# schematic.net
KiCad netlist of a schematic drawn in Altium Designer
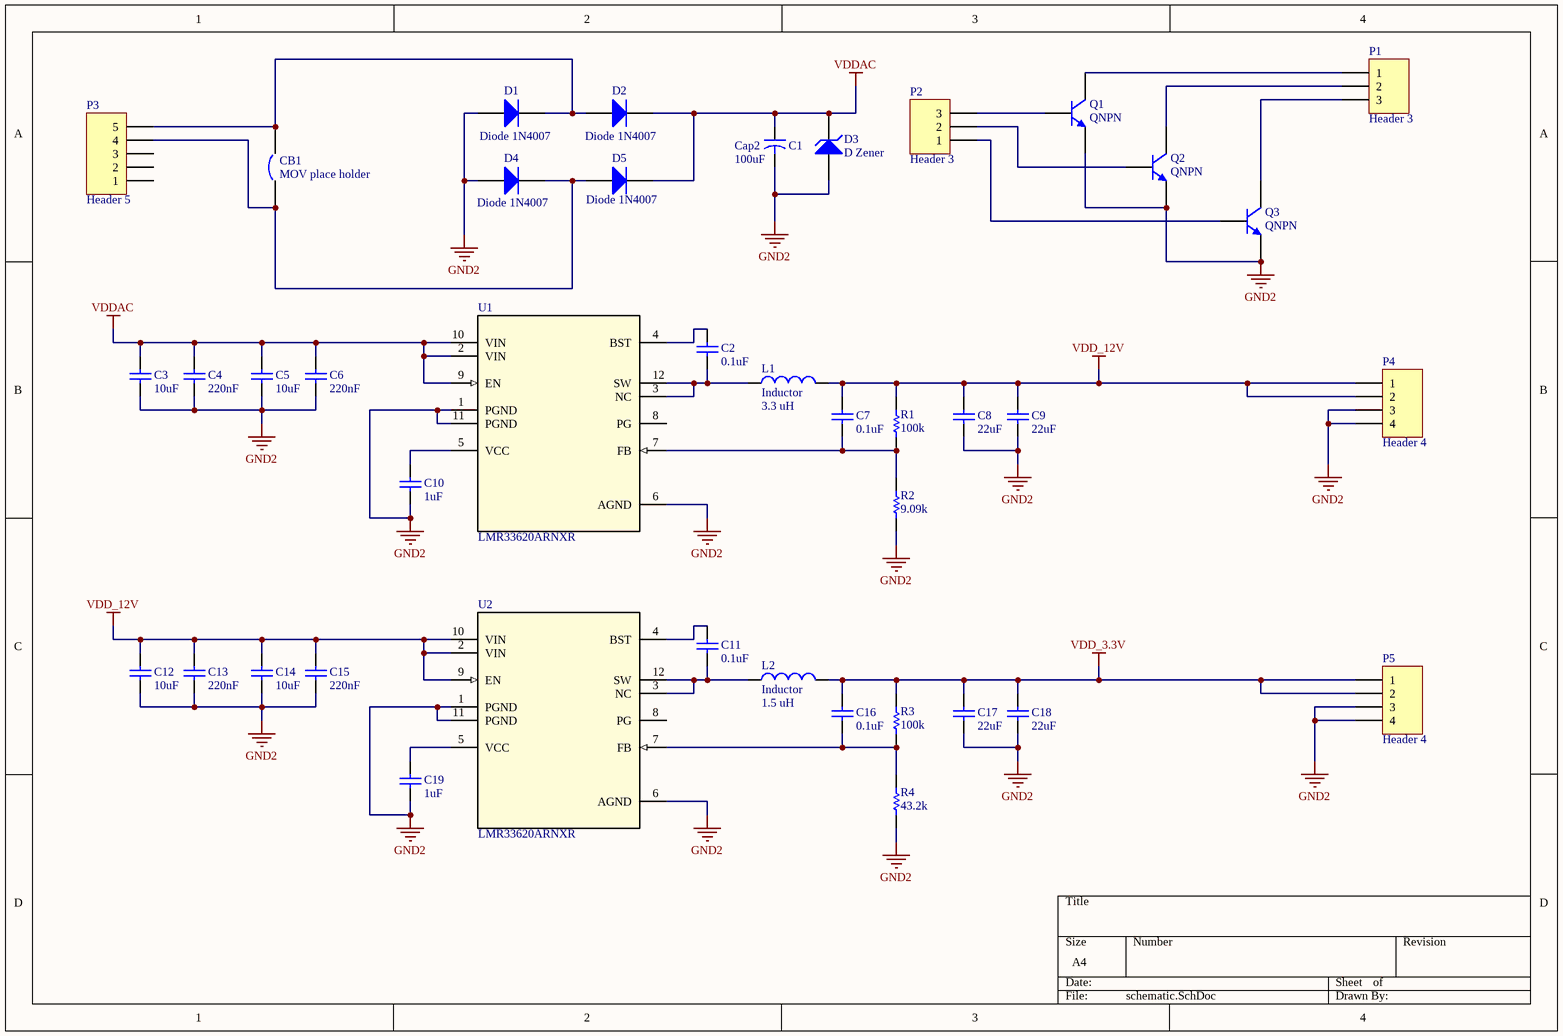
[diagram p0: schematic.SchDoc]

(export (version "E")
  (design (tool "Eeschema 10.0.6"))
  (components
    (comp (ref "C1")
      (value "Cap2")
      (footprint "CAPR5-4X5")
      (description "Capacitor")
      (fields (field (name "ALTIUM_VALUE") "100uF") (field (name "PUBLISHER") "Altium Limited"))
      (libsource (lib "Miscellaneous Devices") (part "Cap2"))
    )
    (comp (ref "C2")
      (value "0.1uF")
      (footprint "C_0402")
      (libsource (lib "Miscellaneous Devices") (part "Cap"))
    )
    (comp (ref "C3")
      (value "10uF")
      (footprint "CAPC1608X05N")
      (libsource (lib "Miscellaneous Devices") (part "Cap"))
    )
    (comp (ref "C4")
      (value "220nF")
      (footprint "C_0402")
      (libsource (lib "Miscellaneous Devices") (part "Cap"))
    )
    (comp (ref "C5")
      (value "10uF")
      (footprint "CAPC1608X05N")
      (libsource (lib "Miscellaneous Devices") (part "Cap"))
    )
    (comp (ref "C6")
      (value "220nF")
      (footprint "C_0402")
      (libsource (lib "Miscellaneous Devices") (part "Cap"))
    )
    (comp (ref "C7")
      (value "0.1uF")
      (footprint "C_0402")
      (libsource (lib "Miscellaneous Devices") (part "Cap"))
    )
    (comp (ref "C8")
      (value "22uF")
      (footprint "CAPC1608X05N")
      (libsource (lib "Miscellaneous Devices") (part "Cap"))
    )
    (comp (ref "C9")
      (value "22uF")
      (footprint "CAPC1608X05N")
      (libsource (lib "Miscellaneous Devices") (part "Cap"))
    )
    (comp (ref "C10")
      (value "1uF")
      (footprint "C_0402")
      (libsource (lib "Miscellaneous Devices") (part "Cap"))
    )
    (comp (ref "C11")
      (value "0.1uF")
      (footprint "C_0402")
      (libsource (lib "Miscellaneous Devices") (part "Cap"))
    )
    (comp (ref "C12")
      (value "10uF")
      (footprint "CAPC1608X05N")
      (libsource (lib "Miscellaneous Devices") (part "Cap"))
    )
    (comp (ref "C13")
      (value "220nF")
      (footprint "C_0402")
      (libsource (lib "Miscellaneous Devices") (part "Cap"))
    )
    (comp (ref "C14")
      (value "10uF")
      (footprint "CAPC1608X05N")
      (libsource (lib "Miscellaneous Devices") (part "Cap"))
    )
    (comp (ref "C15")
      (value "220nF")
      (footprint "C_0402")
      (libsource (lib "Miscellaneous Devices") (part "Cap"))
    )
    (comp (ref "C16")
      (value "0.1uF")
      (footprint "C_0402")
      (libsource (lib "Miscellaneous Devices") (part "Cap"))
    )
    (comp (ref "C17")
      (value "22uF")
      (footprint "CAPC1608X05N")
      (libsource (lib "Miscellaneous Devices") (part "Cap"))
    )
    (comp (ref "C18")
      (value "22uF")
      (footprint "CAPC1608X05N")
      (libsource (lib "Miscellaneous Devices") (part "Cap"))
    )
    (comp (ref "C19")
      (value "1uF")
      (footprint "C_0402")
      (libsource (lib "Miscellaneous Devices") (part "Cap"))
    )
    (comp (ref "CB1")
      (value "MOV place holder")
      (footprint "mov")
      (description "Circuit Breaker")
      (fields (field (name "PUBLISHER") "Altium Limited"))
      (libsource (lib "Miscellaneous Devices") (part "Circuit Breaker"))
    )
    (comp (ref "D1")
      (value "Diode 1N4007")
      (footprint "DO-41")
      (description "1 Amp General Purpose Rectifier")
      (fields (field (name "PUBLISHER") "Altium Limited"))
      (libsource (lib "Miscellaneous Devices") (part "Diode 1N4007"))
    )
    (comp (ref "D2")
      (value "Diode 1N4007")
      (footprint "DO-41")
      (description "1 Amp General Purpose Rectifier")
      (fields (field (name "PUBLISHER") "Altium Limited"))
      (libsource (lib "Miscellaneous Devices") (part "Diode 1N4007"))
    )
    (comp (ref "D3")
      (value "D Zener")
      (footprint "DIODE")
      (description "Zener Diode")
      (fields (field (name "PUBLISHER") "Altium Limited"))
      (libsource (lib "Miscellaneous Devices") (part "D Zener"))
    )
    (comp (ref "D4")
      (value "Diode 1N4007")
      (footprint "DO-41")
      (description "1 Amp General Purpose Rectifier")
      (fields (field (name "PUBLISHER") "Altium Limited"))
      (libsource (lib "Miscellaneous Devices") (part "Diode 1N4007"))
    )
    (comp (ref "D5")
      (value "Diode 1N4007")
      (footprint "DO-41")
      (description "1 Amp General Purpose Rectifier")
      (fields (field (name "PUBLISHER") "Altium Limited"))
      (libsource (lib "Miscellaneous Devices") (part "Diode 1N4007"))
    )
    (comp (ref "L1")
      (value "Inductor")
      (footprint "INDC2016X10N")
      (fields (field (name "ALTIUM_VALUE") "3.3 uH") (field (name "PUBLISHER") "Altium Limited"))
      (libsource (lib "Miscellaneous Devices") (part "Inductor"))
    )
    (comp (ref "L2")
      (value "Inductor")
      (footprint "INDC2016X10N")
      (fields (field (name "ALTIUM_VALUE") "1.5 uH") (field (name "PUBLISHER") "Altium Limited"))
      (libsource (lib "Miscellaneous Devices") (part "Inductor"))
    )
    (comp (ref "P1")
      (value "Header 3")
      (footprint "HDR1X3")
      (description "Header, 3-Pin")
      (fields (field (name "PUBLISHER") "Altium Limited"))
      (libsource (lib "") (part "Header 3_1"))
    )
    (comp (ref "P2")
      (value "Header 3")
      (footprint "HDR1X3")
      (description "Header, 3-Pin")
      (fields (field (name "PUBLISHER") "Altium Limited"))
      (libsource (lib "Miscellaneous Connectors") (part "Header 3"))
    )
    (comp (ref "P3")
      (value "Header 5")
      (footprint "edge")
      (description "Header, 5-Pin")
      (fields (field (name "PUBLISHER") "Altium Limited"))
      (libsource (lib "Miscellaneous Connectors") (part "Header 5"))
    )
    (comp (ref "P4")
      (value "Header 4")
      (footprint "HDR1X4")
      (description "Header, 4-Pin")
      (fields (field (name "PUBLISHER") "Altium Limited"))
      (libsource (lib "Miscellaneous Connectors") (part "Header 4"))
    )
    (comp (ref "P5")
      (value "Header 4")
      (footprint "HDR1X4")
      (description "Header, 4-Pin")
      (fields (field (name "PUBLISHER") "Altium Limited"))
      (libsource (lib "Miscellaneous Connectors") (part "Header 4"))
    )
    (comp (ref "Q1")
      (value "QNPN")
      (footprint "SOT-23B_N")
      (description "NPN Bipolar Transistor")
      (fields (field (name "PUBLISHER") "Altium Limited"))
      (libsource (lib "Miscellaneous Devices") (part "QNPN"))
    )
    (comp (ref "Q2")
      (value "QNPN")
      (footprint "SOT-23B_N")
      (description "NPN Bipolar Transistor")
      (fields (field (name "PUBLISHER") "Altium Limited"))
      (libsource (lib "Miscellaneous Devices") (part "QNPN"))
    )
    (comp (ref "Q3")
      (value "QNPN")
      (footprint "SOT-23B_N")
      (description "NPN Bipolar Transistor")
      (fields (field (name "PUBLISHER") "Altium Limited"))
      (libsource (lib "Miscellaneous Devices") (part "QNPN"))
    )
    (comp (ref "R1")
      (value "Res1")
      (footprint "R_0402")
      (description "Resistor")
      (fields (field (name "ALTIUM_UNNAMED_1") "100k"))
      (libsource (lib "Miscellaneous Devices") (part "Res1"))
    )
    (comp (ref "R2")
      (value "Res1")
      (footprint "R_0402")
      (description "Resistor")
      (fields (field (name "ALTIUM_UNNAMED_1") "9.09k"))
      (libsource (lib "Miscellaneous Devices") (part "Res1"))
    )
    (comp (ref "R3")
      (value "Res1")
      (footprint "R_0402")
      (description "Resistor")
      (fields (field (name "ALTIUM_UNNAMED_1") "100k"))
      (libsource (lib "Miscellaneous Devices") (part "Res1"))
    )
    (comp (ref "R4")
      (value "Res1")
      (footprint "R_0402")
      (description "Resistor")
      (fields (field (name "ALTIUM_UNNAMED_1") "43.2k"))
      (libsource (lib "Miscellaneous Devices") (part "Res1"))
    )
    (comp (ref "U1")
      (value "LMR33620ARNXR")
      (footprint "RNX0012B")
      (description "Imported")
      (fields (field (name "MANUFACTURER") "Texas Instruments"))
      (libsource (lib "LMR33620") (part "LMR33620ARNXR"))
    )
    (comp (ref "U2")
      (value "LMR33620ARNXR")
      (footprint "RNX0012B")
      (description "Imported")
      (fields (field (name "MANUFACTURER") "Texas Instruments"))
      (libsource (lib "LMR33620") (part "LMR33620ARNXR"))
    )
  )
  (nets
    (net (code "1") (name "GND2") (class "Default")
      (node (ref "C1") (pin "2") (pinfunction "2_2") (pintype "passive"))
      (node (ref "C10") (pin "1") (pinfunction "1_1") (pintype "passive"))
      (node (ref "C12") (pin "1") (pinfunction "1_1") (pintype "passive"))
      (node (ref "C13") (pin "1") (pinfunction "1_1") (pintype "passive"))
      (node (ref "C14") (pin "1") (pinfunction "1_1") (pintype "passive"))
      (node (ref "C15") (pin "1") (pinfunction "1_1") (pintype "passive"))
      (node (ref "C17") (pin "1") (pinfunction "1_1") (pintype "passive"))
      (node (ref "C18") (pin "1") (pinfunction "1_1") (pintype "passive"))
      (node (ref "C19") (pin "1") (pinfunction "1_1") (pintype "passive"))
      (node (ref "C3") (pin "1") (pinfunction "1_1") (pintype "passive"))
      (node (ref "C4") (pin "1") (pinfunction "1_1") (pintype "passive"))
      (node (ref "C5") (pin "1") (pinfunction "1_1") (pintype "passive"))
      (node (ref "C6") (pin "1") (pinfunction "1_1") (pintype "passive"))
      (node (ref "C8") (pin "1") (pinfunction "1_1") (pintype "passive"))
      (node (ref "C9") (pin "1") (pinfunction "1_1") (pintype "passive"))
      (node (ref "D1") (pin "1") (pinfunction "A_1") (pintype "passive"))
      (node (ref "D3") (pin "1") (pinfunction "A_1") (pintype "passive"))
      (node (ref "D4") (pin "1") (pinfunction "A_1") (pintype "passive"))
      (node (ref "P4") (pin "3") (pinfunction "3_3") (pintype "passive"))
      (node (ref "P4") (pin "4") (pinfunction "4_4") (pintype "passive"))
      (node (ref "P5") (pin "3") (pinfunction "3_3") (pintype "passive"))
      (node (ref "P5") (pin "4") (pinfunction "4_4") (pintype "passive"))
      (node (ref "Q1") (pin "2") (pinfunction "E_2") (pintype "passive"))
      (node (ref "Q2") (pin "2") (pinfunction "E_2") (pintype "passive"))
      (node (ref "Q3") (pin "2") (pinfunction "E_2") (pintype "passive"))
      (node (ref "R2") (pin "2") (pinfunction "2_2") (pintype "passive"))
      (node (ref "R4") (pin "2") (pinfunction "2_2") (pintype "passive"))
      (node (ref "U1") (pin "1") (pinfunction "PGND_1") (pintype "power_in"))
      (node (ref "U1") (pin "11") (pinfunction "PGND_11") (pintype "power_in"))
      (node (ref "U1") (pin "6") (pinfunction "AGND_6") (pintype "power_in"))
      (node (ref "U2") (pin "1") (pinfunction "PGND_1") (pintype "power_in"))
      (node (ref "U2") (pin "11") (pinfunction "PGND_11") (pintype "power_in"))
      (node (ref "U2") (pin "6") (pinfunction "AGND_6") (pintype "power_in"))
    )
    (net (code "2") (name "Net-(D1-K)") (class "Default")
      (node (ref "CB1") (pin "2") (pinfunction "2_2") (pintype "passive"))
      (node (ref "D1") (pin "2") (pinfunction "K_2") (pintype "passive"))
      (node (ref "D2") (pin "1") (pinfunction "A_1") (pintype "passive"))
      (node (ref "P3") (pin "5") (pinfunction "5_5") (pintype "passive"))
    )
    (net (code "3") (name "Net-(D4-K)") (class "Default")
      (node (ref "CB1") (pin "1") (pinfunction "1_1") (pintype "passive"))
      (node (ref "D4") (pin "2") (pinfunction "K_2") (pintype "passive"))
      (node (ref "D5") (pin "1") (pinfunction "A_1") (pintype "passive"))
      (node (ref "P3") (pin "4") (pinfunction "4_4") (pintype "passive"))
    )
    (net (code "4") (name "Net-(Q1-B)") (class "Default")
      (node (ref "P2") (pin "3") (pinfunction "3_3") (pintype "passive"))
      (node (ref "Q1") (pin "1") (pinfunction "B_1") (pintype "passive"))
    )
    (net (code "5") (name "Net-(Q1-C)") (class "Default")
      (node (ref "P1") (pin "1") (pinfunction "1_1") (pintype "passive"))
      (node (ref "Q1") (pin "3") (pinfunction "C_3") (pintype "passive"))
    )
    (net (code "6") (name "Net-(Q2-B)") (class "Default")
      (node (ref "P2") (pin "2") (pinfunction "2_2") (pintype "passive"))
      (node (ref "Q2") (pin "1") (pinfunction "B_1") (pintype "passive"))
    )
    (net (code "7") (name "Net-(Q2-C)") (class "Default")
      (node (ref "P1") (pin "2") (pinfunction "2_2") (pintype "passive"))
      (node (ref "Q2") (pin "3") (pinfunction "C_3") (pintype "passive"))
    )
    (net (code "8") (name "Net-(Q3-B)") (class "Default")
      (node (ref "P2") (pin "1") (pinfunction "1_1") (pintype "passive"))
      (node (ref "Q3") (pin "1") (pinfunction "B_1") (pintype "passive"))
    )
    (net (code "9") (name "Net-(Q3-C)") (class "Default")
      (node (ref "P1") (pin "3") (pinfunction "3_3") (pintype "passive"))
      (node (ref "Q3") (pin "3") (pinfunction "C_3") (pintype "passive"))
    )
    (net (code "10") (name "Net-(U1-BST)") (class "Default")
      (node (ref "C2") (pin "2") (pinfunction "2_2") (pintype "passive"))
      (node (ref "U1") (pin "4") (pinfunction "BST_4") (pintype "passive"))
    )
    (net (code "11") (name "Net-(U1-FB)") (class "Default")
      (node (ref "C7") (pin "1") (pinfunction "1_1") (pintype "passive"))
      (node (ref "R1") (pin "2") (pinfunction "2_2") (pintype "passive"))
      (node (ref "R2") (pin "1") (pinfunction "1_1") (pintype "passive"))
      (node (ref "U1") (pin "7") (pinfunction "FB_7") (pintype "input"))
    )
    (net (code "12") (name "Net-(U1-NC)") (class "Default")
      (node (ref "C2") (pin "1") (pinfunction "1_1") (pintype "passive"))
      (node (ref "L1") (pin "1") (pinfunction "1_1") (pintype "passive"))
      (node (ref "U1") (pin "12") (pinfunction "SW_12") (pintype "power_in"))
      (node (ref "U1") (pin "3") (pinfunction "NC_3") (pintype "passive"))
    )
    (net (code "13") (name "Net-(U1-VCC)") (class "Default")
      (node (ref "C10") (pin "2") (pinfunction "2_2") (pintype "passive"))
      (node (ref "U1") (pin "5") (pinfunction "VCC_5") (pintype "power_in"))
    )
    (net (code "14") (name "Net-(U2-BST)") (class "Default")
      (node (ref "C11") (pin "2") (pinfunction "2_2") (pintype "passive"))
      (node (ref "U2") (pin "4") (pinfunction "BST_4") (pintype "passive"))
    )
    (net (code "15") (name "Net-(U2-FB)") (class "Default")
      (node (ref "C16") (pin "1") (pinfunction "1_1") (pintype "passive"))
      (node (ref "R3") (pin "2") (pinfunction "2_2") (pintype "passive"))
      (node (ref "R4") (pin "1") (pinfunction "1_1") (pintype "passive"))
      (node (ref "U2") (pin "7") (pinfunction "FB_7") (pintype "input"))
    )
    (net (code "16") (name "Net-(U2-NC)") (class "Default")
      (node (ref "C11") (pin "1") (pinfunction "1_1") (pintype "passive"))
      (node (ref "L2") (pin "1") (pinfunction "1_1") (pintype "passive"))
      (node (ref "U2") (pin "12") (pinfunction "SW_12") (pintype "power_in"))
      (node (ref "U2") (pin "3") (pinfunction "NC_3") (pintype "passive"))
    )
    (net (code "17") (name "Net-(U2-VCC)") (class "Default")
      (node (ref "C19") (pin "2") (pinfunction "2_2") (pintype "passive"))
      (node (ref "U2") (pin "5") (pinfunction "VCC_5") (pintype "power_in"))
    )
    (net (code "18") (name "VDDAC") (class "Default")
      (node (ref "C1") (pin "1") (pinfunction "1_1") (pintype "passive"))
      (node (ref "C3") (pin "2") (pinfunction "2_2") (pintype "passive"))
      (node (ref "C4") (pin "2") (pinfunction "2_2") (pintype "passive"))
      (node (ref "C5") (pin "2") (pinfunction "2_2") (pintype "passive"))
      (node (ref "C6") (pin "2") (pinfunction "2_2") (pintype "passive"))
      (node (ref "D2") (pin "2") (pinfunction "K_2") (pintype "passive"))
      (node (ref "D3") (pin "2") (pinfunction "K_2") (pintype "passive"))
      (node (ref "D5") (pin "2") (pinfunction "K_2") (pintype "passive"))
      (node (ref "U1") (pin "10") (pinfunction "VIN_10") (pintype "power_in"))
      (node (ref "U1") (pin "2") (pinfunction "VIN_2") (pintype "power_in"))
      (node (ref "U1") (pin "9") (pinfunction "EN_9") (pintype "input"))
    )
    (net (code "19") (name "VDD_3.3V") (class "Default")
      (node (ref "C16") (pin "2") (pinfunction "2_2") (pintype "passive"))
      (node (ref "C17") (pin "2") (pinfunction "2_2") (pintype "passive"))
      (node (ref "C18") (pin "2") (pinfunction "2_2") (pintype "passive"))
      (node (ref "L2") (pin "2") (pinfunction "2_2") (pintype "passive"))
      (node (ref "P5") (pin "1") (pinfunction "1_1") (pintype "passive"))
      (node (ref "P5") (pin "2") (pinfunction "2_2") (pintype "passive"))
      (node (ref "R3") (pin "1") (pinfunction "1_1") (pintype "passive"))
    )
    (net (code "20") (name "VDD_12V") (class "Default")
      (node (ref "C12") (pin "2") (pinfunction "2_2") (pintype "passive"))
      (node (ref "C13") (pin "2") (pinfunction "2_2") (pintype "passive"))
      (node (ref "C14") (pin "2") (pinfunction "2_2") (pintype "passive"))
      (node (ref "C15") (pin "2") (pinfunction "2_2") (pintype "passive"))
      (node (ref "C7") (pin "2") (pinfunction "2_2") (pintype "passive"))
      (node (ref "C8") (pin "2") (pinfunction "2_2") (pintype "passive"))
      (node (ref "C9") (pin "2") (pinfunction "2_2") (pintype "passive"))
      (node (ref "L1") (pin "2") (pinfunction "2_2") (pintype "passive"))
      (node (ref "P4") (pin "1") (pinfunction "1_1") (pintype "passive"))
      (node (ref "P4") (pin "2") (pinfunction "2_2") (pintype "passive"))
      (node (ref "R1") (pin "1") (pinfunction "1_1") (pintype "passive"))
      (node (ref "U2") (pin "10") (pinfunction "VIN_10") (pintype "power_in"))
      (node (ref "U2") (pin "2") (pinfunction "VIN_2") (pintype "power_in"))
      (node (ref "U2") (pin "9") (pinfunction "EN_9") (pintype "input"))
    )
    (net (code "21") (name "unconnected-(P3-Pad1)") (class "Default")
      (node (ref "P3") (pin "1") (pinfunction "1_1") (pintype "passive"))
    )
    (net (code "22") (name "unconnected-(P3-Pad2)") (class "Default")
      (node (ref "P3") (pin "2") (pinfunction "2_2") (pintype "passive"))
    )
    (net (code "23") (name "unconnected-(P3-Pad3)") (class "Default")
      (node (ref "P3") (pin "3") (pinfunction "3_3") (pintype "passive"))
    )
    (net (code "24") (name "unconnected-(U1-PG-Pad8)") (class "Default")
      (node (ref "U1") (pin "8") (pinfunction "PG_8") (pintype "open_collector"))
    )
    (net (code "25") (name "unconnected-(U2-PG-Pad8)") (class "Default")
      (node (ref "U2") (pin "8") (pinfunction "PG_8") (pintype "open_collector"))
    )
  )
)
